# usomiq.net
KiCad netlist of a schematic drawn in Altium Designer
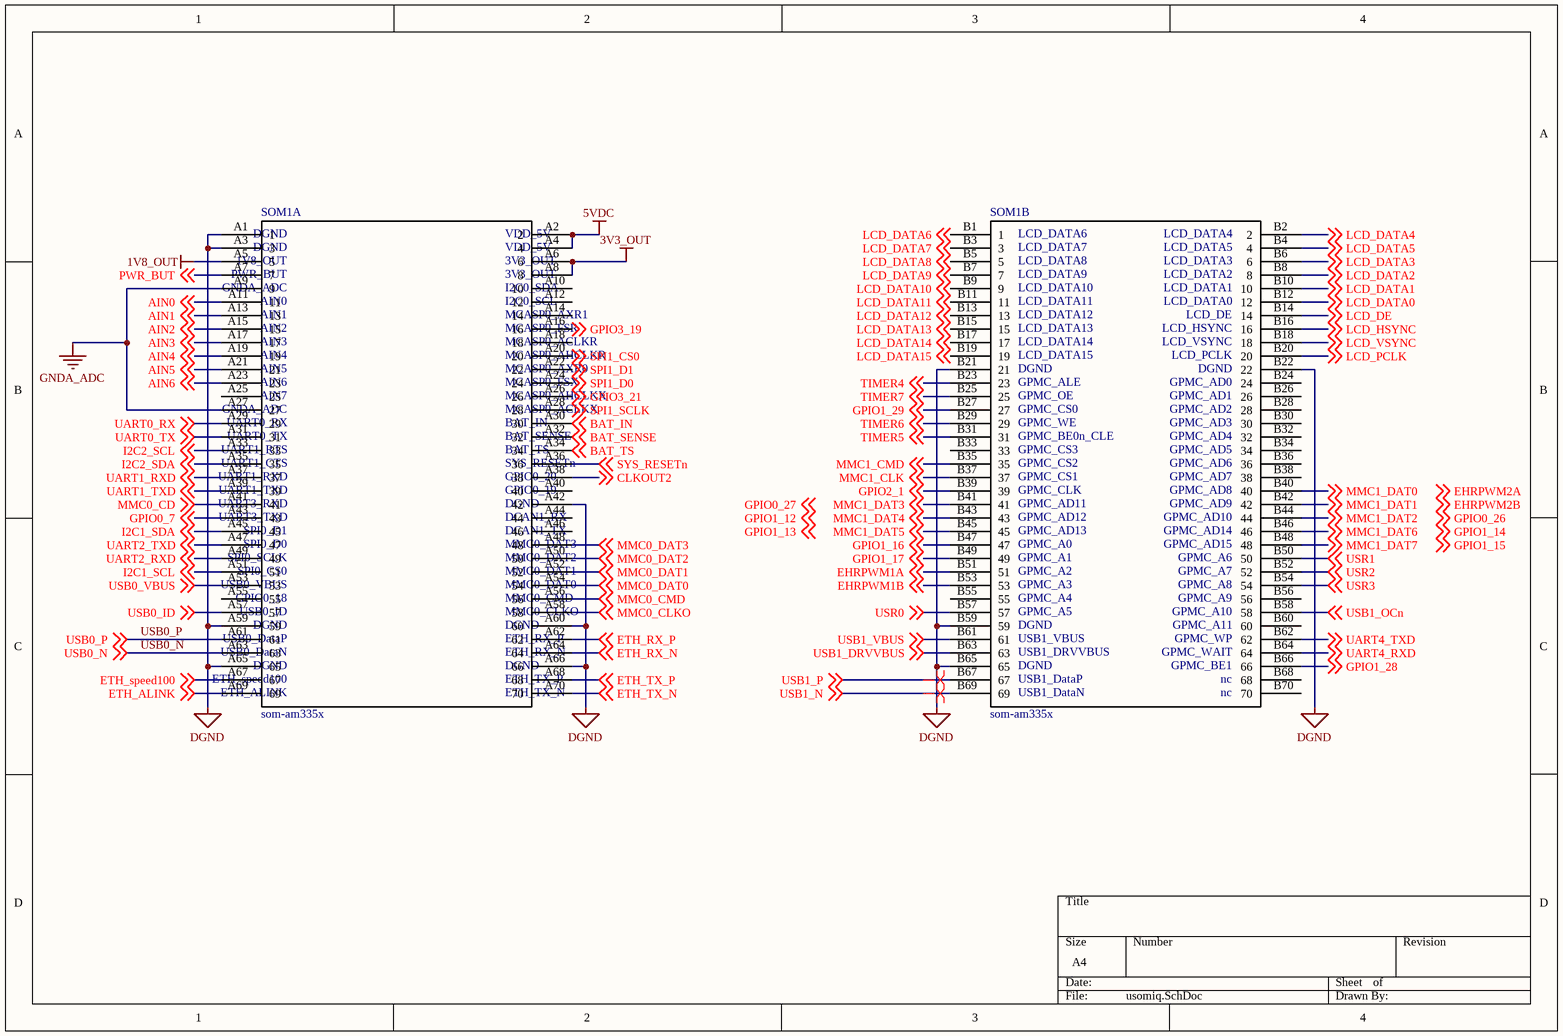
[diagram p0: usomiq.SchDoc]

(export (version "E")
  (design (tool "Eeschema 10.0.6"))
  (components
    (comp (ref "SOM1")
      (value "som-am335x")
      (footprint "am3359_module-sockets")
      (libsource (lib "usomiq-base") (part "som-am335x"))
    )
  )
  (nets
    (net (code "1") (name "1V8_OUT") (class "Default")
      (node (ref "SOM1") (pin "A5") (pinfunction "5_A5") (pintype "passive"))
    )
    (net (code "2") (name "3V3_OUT") (class "Default")
      (node (ref "SOM1") (pin "A6") (pinfunction "6_A6") (pintype "passive"))
      (node (ref "SOM1") (pin "A8") (pinfunction "8_A8") (pintype "passive"))
    )
    (net (code "3") (name "5VDC") (class "Default")
      (node (ref "SOM1") (pin "A2") (pinfunction "2_A2") (pintype "passive"))
      (node (ref "SOM1") (pin "A4") (pinfunction "4_A4") (pintype "passive"))
    )
    (net (code "4") (name "AIN0") (class "Default")
      (node (ref "SOM1") (pin "A11") (pinfunction "11_A11") (pintype "passive"))
    )
    (net (code "5") (name "AIN1") (class "Default")
      (node (ref "SOM1") (pin "A13") (pinfunction "13_A13") (pintype "passive"))
    )
    (net (code "6") (name "AIN2") (class "Default")
      (node (ref "SOM1") (pin "A15") (pinfunction "15_A15") (pintype "passive"))
    )
    (net (code "7") (name "AIN3") (class "Default")
      (node (ref "SOM1") (pin "A17") (pinfunction "17_A17") (pintype "passive"))
    )
    (net (code "8") (name "AIN4") (class "Default")
      (node (ref "SOM1") (pin "A19") (pinfunction "19_A19") (pintype "passive"))
    )
    (net (code "9") (name "AIN5") (class "Default")
      (node (ref "SOM1") (pin "A21") (pinfunction "21_A21") (pintype "passive"))
    )
    (net (code "10") (name "AIN6") (class "Default")
      (node (ref "SOM1") (pin "A23") (pinfunction "23_A23") (pintype "passive"))
    )
    (net (code "11") (name "BAT_IN") (class "Default")
      (node (ref "SOM1") (pin "A30") (pinfunction "30_A30") (pintype "passive"))
    )
    (net (code "12") (name "BAT_SENSE") (class "Default")
      (node (ref "SOM1") (pin "A32") (pinfunction "32_A32") (pintype "passive"))
    )
    (net (code "13") (name "BAT_TS") (class "Default")
      (node (ref "SOM1") (pin "A34") (pinfunction "34_A34") (pintype "passive"))
    )
    (net (code "14") (name "CLKOUT2") (class "Default")
      (node (ref "SOM1") (pin "A38") (pinfunction "38_A38") (pintype "passive"))
    )
    (net (code "15") (name "DGND") (class "Default")
      (node (ref "SOM1") (pin "A1") (pinfunction "1_A1") (pintype "passive"))
      (node (ref "SOM1") (pin "A3") (pinfunction "3_A3") (pintype "passive"))
      (node (ref "SOM1") (pin "A42") (pinfunction "42_A42") (pintype "passive"))
      (node (ref "SOM1") (pin "A59") (pinfunction "59_A59") (pintype "passive"))
      (node (ref "SOM1") (pin "A60") (pinfunction "60_A60") (pintype "passive"))
      (node (ref "SOM1") (pin "A65") (pinfunction "65_A65") (pintype "passive"))
      (node (ref "SOM1") (pin "A66") (pinfunction "66_A66") (pintype "passive"))
      (node (ref "SOM1") (pin "B21") (pinfunction "21_B21") (pintype "passive"))
      (node (ref "SOM1") (pin "B22") (pinfunction "22_B22") (pintype "passive"))
      (node (ref "SOM1") (pin "B59") (pinfunction "59_B59") (pintype "passive"))
      (node (ref "SOM1") (pin "B65") (pinfunction "65_B65") (pintype "passive"))
    )
    (net (code "16") (name "EHRPWM1A") (class "Default")
      (node (ref "SOM1") (pin "B51") (pinfunction "51_B51") (pintype "passive"))
    )
    (net (code "17") (name "EHRPWM1B") (class "Default")
      (node (ref "SOM1") (pin "B53") (pinfunction "53_B53") (pintype "passive"))
    )
    (net (code "20") (name "ETH_ALINK") (class "Default")
      (node (ref "SOM1") (pin "A69") (pinfunction "69_A69") (pintype "passive"))
    )
    (net (code "21") (name "ETH_RX_N") (class "Default")
      (node (ref "SOM1") (pin "A64") (pinfunction "64_A64") (pintype "passive"))
    )
    (net (code "22") (name "ETH_RX_P") (class "Default")
      (node (ref "SOM1") (pin "A62") (pinfunction "62_A62") (pintype "passive"))
    )
    (net (code "23") (name "ETH_TX_N") (class "Default")
      (node (ref "SOM1") (pin "A70") (pinfunction "70_A70") (pintype "passive"))
    )
    (net (code "24") (name "ETH_TX_P") (class "Default")
      (node (ref "SOM1") (pin "A68") (pinfunction "68_A68") (pintype "passive"))
    )
    (net (code "25") (name "ETH_speed100") (class "Default")
      (node (ref "SOM1") (pin "A67") (pinfunction "67_A67") (pintype "passive"))
    )
    (net (code "26") (name "GNDA_ADC") (class "Default")
      (node (ref "SOM1") (pin "A27") (pinfunction "27_A27") (pintype "passive"))
      (node (ref "SOM1") (pin "A9") (pinfunction "9_A9") (pintype "passive"))
    )
    (net (code "27") (name "GPIO0_7") (class "Default")
      (node (ref "SOM1") (pin "A43") (pinfunction "43_A43") (pintype "passive"))
    )
    (net (code "34") (name "GPIO1_16") (class "Default")
      (node (ref "SOM1") (pin "B47") (pinfunction "47_B47") (pintype "passive"))
    )
    (net (code "35") (name "GPIO1_17") (class "Default")
      (node (ref "SOM1") (pin "B49") (pinfunction "49_B49") (pintype "passive"))
    )
    (net (code "36") (name "GPIO1_28") (class "Default")
      (node (ref "SOM1") (pin "B66") (pinfunction "66_B66") (pintype "passive"))
    )
    (net (code "37") (name "GPIO1_29") (class "Default")
      (node (ref "SOM1") (pin "B27") (pinfunction "27_B27") (pintype "passive"))
    )
    (net (code "38") (name "GPIO2_1") (class "Default")
      (node (ref "SOM1") (pin "B39") (pinfunction "39_B39") (pintype "passive"))
    )
    (net (code "39") (name "GPIO3_19") (class "Default")
      (node (ref "SOM1") (pin "A16") (pinfunction "16_A16") (pintype "passive"))
    )
    (net (code "40") (name "GPIO3_21") (class "Default")
      (node (ref "SOM1") (pin "A26") (pinfunction "26_A26") (pintype "passive"))
    )
    (net (code "41") (name "I2C1_SCL") (class "Default")
      (node (ref "SOM1") (pin "A51") (pinfunction "51_A51") (pintype "passive"))
    )
    (net (code "42") (name "I2C1_SDA") (class "Default")
      (node (ref "SOM1") (pin "A45") (pinfunction "45_A45") (pintype "passive"))
    )
    (net (code "43") (name "I2C2_SCL") (class "Default")
      (node (ref "SOM1") (pin "A33") (pinfunction "33_A33") (pintype "passive"))
    )
    (net (code "44") (name "I2C2_SDA") (class "Default")
      (node (ref "SOM1") (pin "A35") (pinfunction "35_A35") (pintype "passive"))
    )
    (net (code "45") (name "LCD_DATA0") (class "Default")
      (node (ref "SOM1") (pin "B12") (pinfunction "12_B12") (pintype "passive"))
    )
    (net (code "46") (name "LCD_DATA1") (class "Default")
      (node (ref "SOM1") (pin "B10") (pinfunction "10_B10") (pintype "passive"))
    )
    (net (code "47") (name "LCD_DATA2") (class "Default")
      (node (ref "SOM1") (pin "B8") (pinfunction "8_B8") (pintype "passive"))
    )
    (net (code "48") (name "LCD_DATA3") (class "Default")
      (node (ref "SOM1") (pin "B6") (pinfunction "6_B6") (pintype "passive"))
    )
    (net (code "49") (name "LCD_DATA4") (class "Default")
      (node (ref "SOM1") (pin "B2") (pinfunction "2_B2") (pintype "passive"))
    )
    (net (code "50") (name "LCD_DATA5") (class "Default")
      (node (ref "SOM1") (pin "B4") (pinfunction "4_B4") (pintype "passive"))
    )
    (net (code "51") (name "LCD_DATA6") (class "Default")
      (node (ref "SOM1") (pin "B1") (pinfunction "1_B1") (pintype "passive"))
    )
    (net (code "52") (name "LCD_DATA7") (class "Default")
      (node (ref "SOM1") (pin "B3") (pinfunction "3_B3") (pintype "passive"))
    )
    (net (code "53") (name "LCD_DATA8") (class "Default")
      (node (ref "SOM1") (pin "B5") (pinfunction "5_B5") (pintype "passive"))
    )
    (net (code "54") (name "LCD_DATA9") (class "Default")
      (node (ref "SOM1") (pin "B7") (pinfunction "7_B7") (pintype "passive"))
    )
    (net (code "55") (name "LCD_DATA10") (class "Default")
      (node (ref "SOM1") (pin "B9") (pinfunction "9_B9") (pintype "passive"))
    )
    (net (code "56") (name "LCD_DATA11") (class "Default")
      (node (ref "SOM1") (pin "B11") (pinfunction "11_B11") (pintype "passive"))
    )
    (net (code "57") (name "LCD_DATA12") (class "Default")
      (node (ref "SOM1") (pin "B13") (pinfunction "13_B13") (pintype "passive"))
    )
    (net (code "58") (name "LCD_DATA13") (class "Default")
      (node (ref "SOM1") (pin "B15") (pinfunction "15_B15") (pintype "passive"))
    )
    (net (code "59") (name "LCD_DATA14") (class "Default")
      (node (ref "SOM1") (pin "B17") (pinfunction "17_B17") (pintype "passive"))
    )
    (net (code "60") (name "LCD_DATA15") (class "Default")
      (node (ref "SOM1") (pin "B19") (pinfunction "19_B19") (pintype "passive"))
    )
    (net (code "61") (name "LCD_DE") (class "Default")
      (node (ref "SOM1") (pin "B14") (pinfunction "14_B14") (pintype "passive"))
    )
    (net (code "62") (name "LCD_HSYNC") (class "Default")
      (node (ref "SOM1") (pin "B16") (pinfunction "16_B16") (pintype "passive"))
    )
    (net (code "63") (name "LCD_PCLK") (class "Default")
      (node (ref "SOM1") (pin "B20") (pinfunction "20_B20") (pintype "passive"))
    )
    (net (code "64") (name "LCD_VSYNC") (class "Default")
      (node (ref "SOM1") (pin "B18") (pinfunction "18_B18") (pintype "passive"))
    )
    (net (code "65") (name "MMC0_CD") (class "Default")
      (node (ref "SOM1") (pin "A41") (pinfunction "41_A41") (pintype "passive"))
    )
    (net (code "66") (name "MMC0_CLKO") (class "Default")
      (node (ref "SOM1") (pin "A58") (pinfunction "58_A58") (pintype "passive"))
    )
    (net (code "67") (name "MMC0_CMD") (class "Default")
      (node (ref "SOM1") (pin "A56") (pinfunction "56_A56") (pintype "passive"))
    )
    (net (code "68") (name "MMC0_DAT0") (class "Default")
      (node (ref "SOM1") (pin "A54") (pinfunction "54_A54") (pintype "passive"))
    )
    (net (code "69") (name "MMC0_DAT1") (class "Default")
      (node (ref "SOM1") (pin "A52") (pinfunction "52_A52") (pintype "passive"))
    )
    (net (code "70") (name "MMC0_DAT2") (class "Default")
      (node (ref "SOM1") (pin "A50") (pinfunction "50_A50") (pintype "passive"))
    )
    (net (code "71") (name "MMC0_DAT3") (class "Default")
      (node (ref "SOM1") (pin "A48") (pinfunction "48_A48") (pintype "passive"))
    )
    (net (code "72") (name "MMC1_CLK") (class "Default")
      (node (ref "SOM1") (pin "B37") (pinfunction "37_B37") (pintype "passive"))
    )
    (net (code "73") (name "MMC1_CMD") (class "Default")
      (node (ref "SOM1") (pin "B35") (pinfunction "35_B35") (pintype "passive"))
    )
    (net (code "74") (name "MMC1_DAT0") (class "Default")
      (node (ref "SOM1") (pin "B40") (pinfunction "40_B40") (pintype "passive"))
    )
    (net (code "75") (name "MMC1_DAT1") (class "Default")
      (node (ref "SOM1") (pin "B42") (pinfunction "42_B42") (pintype "passive"))
    )
    (net (code "76") (name "MMC1_DAT2") (class "Default")
      (node (ref "SOM1") (pin "B44") (pinfunction "44_B44") (pintype "passive"))
    )
    (net (code "77") (name "MMC1_DAT3") (class "Default")
      (node (ref "SOM1") (pin "B41") (pinfunction "41_B41") (pintype "passive"))
    )
    (net (code "78") (name "MMC1_DAT4") (class "Default")
      (node (ref "SOM1") (pin "B43") (pinfunction "43_B43") (pintype "passive"))
    )
    (net (code "79") (name "MMC1_DAT5") (class "Default")
      (node (ref "SOM1") (pin "B45") (pinfunction "45_B45") (pintype "passive"))
    )
    (net (code "80") (name "MMC1_DAT6") (class "Default")
      (node (ref "SOM1") (pin "B46") (pinfunction "46_B46") (pintype "passive"))
    )
    (net (code "81") (name "MMC1_DAT7") (class "Default")
      (node (ref "SOM1") (pin "B48") (pinfunction "48_B48") (pintype "passive"))
    )
    (net (code "82") (name "PWR_BUT") (class "Default")
      (node (ref "SOM1") (pin "A7") (pinfunction "7_A7") (pintype "passive"))
    )
    (net (code "83") (name "SPI1_CS0") (class "Default")
      (node (ref "SOM1") (pin "A20") (pinfunction "20_A20") (pintype "passive"))
    )
    (net (code "84") (name "SPI1_D0") (class "Default")
      (node (ref "SOM1") (pin "A24") (pinfunction "24_A24") (pintype "passive"))
    )
    (net (code "85") (name "SPI1_D1") (class "Default")
      (node (ref "SOM1") (pin "A22") (pinfunction "22_A22") (pintype "passive"))
    )
    (net (code "86") (name "SPI1_SCLK") (class "Default")
      (node (ref "SOM1") (pin "A28") (pinfunction "28_A28") (pintype "passive"))
    )
    (net (code "87") (name "SYS_RESETn") (class "Default")
      (node (ref "SOM1") (pin "A36") (pinfunction "36_A36") (pintype "passive"))
    )
    (net (code "88") (name "TIMER4") (class "Default")
      (node (ref "SOM1") (pin "B23") (pinfunction "23_B23") (pintype "passive"))
    )
    (net (code "89") (name "TIMER5") (class "Default")
      (node (ref "SOM1") (pin "B31") (pinfunction "31_B31") (pintype "passive"))
    )
    (net (code "90") (name "TIMER6") (class "Default")
      (node (ref "SOM1") (pin "B29") (pinfunction "29_B29") (pintype "passive"))
    )
    (net (code "91") (name "TIMER7") (class "Default")
      (node (ref "SOM1") (pin "B25") (pinfunction "25_B25") (pintype "passive"))
    )
    (net (code "92") (name "UART0_RX") (class "Default")
      (node (ref "SOM1") (pin "A29") (pinfunction "29_A29") (pintype "passive"))
    )
    (net (code "93") (name "UART0_TX") (class "Default")
      (node (ref "SOM1") (pin "A31") (pinfunction "31_A31") (pintype "passive"))
    )
    (net (code "94") (name "UART1_RXD") (class "Default")
      (node (ref "SOM1") (pin "A37") (pinfunction "37_A37") (pintype "passive"))
    )
    (net (code "95") (name "UART1_TXD") (class "Default")
      (node (ref "SOM1") (pin "A39") (pinfunction "39_A39") (pintype "passive"))
    )
    (net (code "96") (name "UART2_RXD") (class "Default")
      (node (ref "SOM1") (pin "A49") (pinfunction "49_A49") (pintype "passive"))
    )
    (net (code "97") (name "UART2_TXD") (class "Default")
      (node (ref "SOM1") (pin "A47") (pinfunction "47_A47") (pintype "passive"))
    )
    (net (code "98") (name "UART4_RXD") (class "Default")
      (node (ref "SOM1") (pin "B64") (pinfunction "64_B64") (pintype "passive"))
    )
    (net (code "99") (name "UART4_TXD") (class "Default")
      (node (ref "SOM1") (pin "B62") (pinfunction "62_B62") (pintype "passive"))
    )
    (net (code "100") (name "USB0_ID") (class "Default")
      (node (ref "SOM1") (pin "A57") (pinfunction "57_A57") (pintype "passive"))
    )
    (net (code "101") (name "USB0_N") (class "Default")
      (node (ref "SOM1") (pin "A63") (pinfunction "63_A63") (pintype "passive"))
    )
    (net (code "102") (name "USB0_P") (class "Default")
      (node (ref "SOM1") (pin "A61") (pinfunction "61_A61") (pintype "passive"))
    )
    (net (code "103") (name "USB0_VBUS") (class "Default")
      (node (ref "SOM1") (pin "A53") (pinfunction "53_A53") (pintype "passive"))
    )
    (net (code "104") (name "USB1_DRVVBUS") (class "Default")
      (node (ref "SOM1") (pin "B63") (pinfunction "63_B63") (pintype "passive"))
    )
    (net (code "105") (name "USB1_N") (class "Default")
      (node (ref "SOM1") (pin "B69") (pinfunction "69_B69") (pintype "passive"))
    )
    (net (code "106") (name "USB1_OCn") (class "Default")
      (node (ref "SOM1") (pin "B58") (pinfunction "58_B58") (pintype "passive"))
    )
    (net (code "107") (name "USB1_P") (class "Default")
      (node (ref "SOM1") (pin "B67") (pinfunction "67_B67") (pintype "passive"))
    )
    (net (code "108") (name "USB1_VBUS") (class "Default")
      (node (ref "SOM1") (pin "B61") (pinfunction "61_B61") (pintype "passive"))
    )
    (net (code "109") (name "USR0") (class "Default")
      (node (ref "SOM1") (pin "B57") (pinfunction "57_B57") (pintype "passive"))
    )
    (net (code "110") (name "USR1") (class "Default")
      (node (ref "SOM1") (pin "B50") (pinfunction "50_B50") (pintype "passive"))
    )
    (net (code "111") (name "USR2") (class "Default")
      (node (ref "SOM1") (pin "B52") (pinfunction "52_B52") (pintype "passive"))
    )
    (net (code "112") (name "USR3") (class "Default")
      (node (ref "SOM1") (pin "B54") (pinfunction "54_B54") (pintype "passive"))
    )
    (net (code "113") (name "unconnected-(SOM1A-10-PadA10)") (class "Default")
      (node (ref "SOM1") (pin "A10") (pinfunction "10_A10") (pintype "passive"))
    )
    (net (code "114") (name "unconnected-(SOM1A-12-PadA12)") (class "Default")
      (node (ref "SOM1") (pin "A12") (pinfunction "12_A12") (pintype "passive"))
    )
    (net (code "115") (name "unconnected-(SOM1A-14-PadA14)") (class "Default")
      (node (ref "SOM1") (pin "A14") (pinfunction "14_A14") (pintype "passive"))
    )
    (net (code "116") (name "unconnected-(SOM1A-18-PadA18)") (class "Default")
      (node (ref "SOM1") (pin "A18") (pinfunction "18_A18") (pintype "passive"))
    )
    (net (code "117") (name "unconnected-(SOM1A-25-PadA25)") (class "Default")
      (node (ref "SOM1") (pin "A25") (pinfunction "25_A25") (pintype "passive"))
    )
    (net (code "118") (name "unconnected-(SOM1A-40-PadA40)") (class "Default")
      (node (ref "SOM1") (pin "A40") (pinfunction "40_A40") (pintype "passive"))
    )
    (net (code "119") (name "unconnected-(SOM1A-44-PadA44)") (class "Default")
      (node (ref "SOM1") (pin "A44") (pinfunction "44_A44") (pintype "passive"))
    )
    (net (code "120") (name "unconnected-(SOM1A-46-PadA46)") (class "Default")
      (node (ref "SOM1") (pin "A46") (pinfunction "46_A46") (pintype "passive"))
    )
    (net (code "121") (name "unconnected-(SOM1A-55-PadA55)") (class "Default")
      (node (ref "SOM1") (pin "A55") (pinfunction "55_A55") (pintype "passive"))
    )
    (net (code "122") (name "unconnected-(SOM1B-24-PadB24)") (class "Default")
      (node (ref "SOM1") (pin "B24") (pinfunction "24_B24") (pintype "passive"))
    )
    (net (code "123") (name "unconnected-(SOM1B-26-PadB26)") (class "Default")
      (node (ref "SOM1") (pin "B26") (pinfunction "26_B26") (pintype "passive"))
    )
    (net (code "124") (name "unconnected-(SOM1B-28-PadB28)") (class "Default")
      (node (ref "SOM1") (pin "B28") (pinfunction "28_B28") (pintype "passive"))
    )
    (net (code "125") (name "unconnected-(SOM1B-30-PadB30)") (class "Default")
      (node (ref "SOM1") (pin "B30") (pinfunction "30_B30") (pintype "passive"))
    )
    (net (code "126") (name "unconnected-(SOM1B-32-PadB32)") (class "Default")
      (node (ref "SOM1") (pin "B32") (pinfunction "32_B32") (pintype "passive"))
    )
    (net (code "127") (name "unconnected-(SOM1B-33-PadB33)") (class "Default")
      (node (ref "SOM1") (pin "B33") (pinfunction "33_B33") (pintype "passive"))
    )
    (net (code "128") (name "unconnected-(SOM1B-34-PadB34)") (class "Default")
      (node (ref "SOM1") (pin "B34") (pinfunction "34_B34") (pintype "passive"))
    )
    (net (code "129") (name "unconnected-(SOM1B-36-PadB36)") (class "Default")
      (node (ref "SOM1") (pin "B36") (pinfunction "36_B36") (pintype "passive"))
    )
    (net (code "130") (name "unconnected-(SOM1B-38-PadB38)") (class "Default")
      (node (ref "SOM1") (pin "B38") (pinfunction "38_B38") (pintype "passive"))
    )
    (net (code "131") (name "unconnected-(SOM1B-55-PadB55)") (class "Default")
      (node (ref "SOM1") (pin "B55") (pinfunction "55_B55") (pintype "passive"))
    )
    (net (code "132") (name "unconnected-(SOM1B-56-PadB56)") (class "Default")
      (node (ref "SOM1") (pin "B56") (pinfunction "56_B56") (pintype "passive"))
    )
    (net (code "133") (name "unconnected-(SOM1B-60-PadB60)") (class "Default")
      (node (ref "SOM1") (pin "B60") (pinfunction "60_B60") (pintype "passive"))
    )
    (net (code "134") (name "unconnected-(SOM1B-68-PadB68)") (class "Default")
      (node (ref "SOM1") (pin "B68") (pinfunction "68_B68") (pintype "passive"))
    )
    (net (code "135") (name "unconnected-(SOM1B-70-PadB70)") (class "Default")
      (node (ref "SOM1") (pin "B70") (pinfunction "70_B70") (pintype "passive"))
    )
  )
)
